# Amplifier.net
KiCad netlist of a schematic drawn in Altium Designer
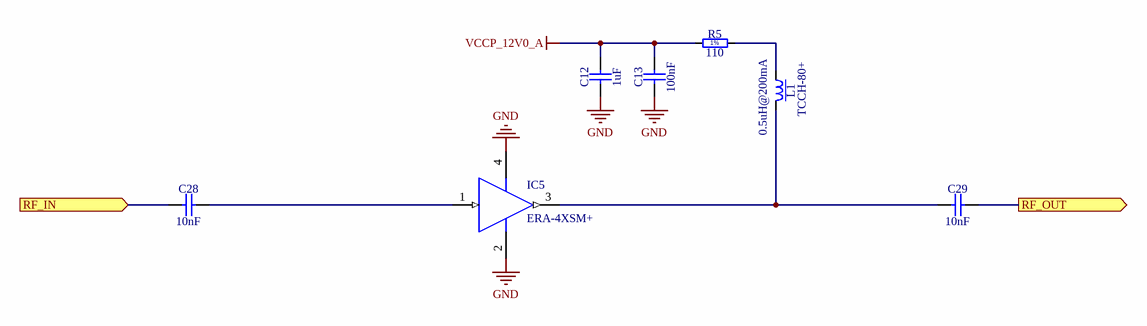
[diagram p0: Amplifier.SchDoc]

(export (version "E")
  (design (tool "Eeschema 10.0.6"))
  (components
    (comp (ref "C12")
      (value "1uF")
      (footprint "CAPC2012X140N")
      (description "Non-polarised capacitor")
      (fields
        (field (name "PART NUMBER") "CC0805_1UF_35V_20%_X7R")
        (field (name "VOLTAGE") "35V")
        (field (name "AUTHOR") "CERN DEM JLC")
      )
      (libsource (lib "Capacitors") (part "Capacitor - non polarized"))
    )
    (comp (ref "C13")
      (value "100nF")
      (footprint "CAPC1608X87N")
      (description "Non-polarised capacitor")
      (fields
        (field (name "PART NUMBER") "CC0603_100NF_50V_10%_X7R")
        (field (name "VOLTAGE") "50V")
        (field (name "AUTHOR") "CERN DEM JLC")
      )
      (libsource (lib "Capacitors") (part "Capacitor - non polarized"))
    )
    (comp (ref "C28")
      (value "10nF")
      (footprint "CAPC1005X55N")
      (description "Non-polarised capacitor")
      (fields
        (field (name "PART NUMBER") "CC0402_10NF_16V_10%_X7R")
        (field (name "VOLTAGE") "16V")
        (field (name "AUTHOR") "CERN DEM JLC")
      )
      (libsource (lib "Capacitors") (part "Capacitor - non polarized"))
    )
    (comp (ref "C29")
      (value "10nF")
      (footprint "CAPC1005X55N")
      (description "Non-polarised capacitor")
      (fields
        (field (name "PART NUMBER") "CC0402_10NF_16V_10%_X7R")
        (field (name "VOLTAGE") "16V")
        (field (name "AUTHOR") "CERN DEM JLC")
      )
      (libsource (lib "Capacitors") (part "Capacitor - non polarized"))
    )
    (comp (ref "IC5")
      (value "ERA-4XSM+")
      (footprint "MINI-CIRCUITS_WW107")
      (description "DC-4GHz Monolithic Amplifier")
      (fields (field (name "MANUFACTURER") "MINI-CIRCUITS") (field (name "AUTHOR") "CERN DEM JMW"))
      (libsource (lib "ICs And Semiconductors") (part "ERA-4XSM+"))
    )
    (comp (ref "L1")
      (value "0.5uH@200mA")
      (footprint "IND_MINI-CIRCUITS_GU1604")
      (description "50 Ohms, 50 to 8200 MHz RF Choke")
      (fields
        (field (name "PART NUMBER") "IND_MINI-CIRCUITS_TCCH-80+")
        (field (name "POWER") "200mA")
        (field (name "MANUFACTURER PART NUMBER") "TCCH-80+")
        (field (name "AUTHOR") "CERN DEM JLC")
      )
      (libsource (lib "Inductors & Transformers") (part "IND_MINI-CIRCUITS_TCCH-80+"))
    )
    (comp (ref "R5")
      (value "110")
      (footprint "RESC1005X40N")
      (description "Resistor - 1%")
      (fields
        (field (name "PART NUMBER") "R0402_110R_1%_0.0625W_100PPM")
        (field (name "POWER") "0.0625W")
        (field (name "AUTHOR") "CERN DEM JLC")
      )
      (libsource (lib "Resistors") (part "Resistor - 1%"))
    )
  )
  (nets
    (net (code "1") (name "/RF_IN") (class "Default")
      (node (ref "C28") (pin "1") (pinfunction "1_1") (pintype "passive"))
    )
    (net (code "2") (name "/RF_OUT") (class "Default")
      (node (ref "C29") (pin "2") (pinfunction "2_2") (pintype "passive"))
    )
    (net (code "3") (name "GND") (class "Default")
      (node (ref "C12") (pin "1") (pinfunction "1_1") (pintype "passive"))
      (node (ref "C13") (pin "1") (pinfunction "1_1") (pintype "passive"))
      (node (ref "IC5") (pin "2") (pinfunction "GND_2") (pintype "power_in"))
      (node (ref "IC5") (pin "4") (pinfunction "GND_4") (pintype "power_in"))
    )
    (net (code "4") (name "Net-(IC5-RF_IN)") (class "Default")
      (node (ref "C28") (pin "2") (pinfunction "2_2") (pintype "passive"))
      (node (ref "IC5") (pin "1") (pinfunction "RF_IN_1") (pintype "input"))
    )
    (net (code "5") (name "Net-(IC5-RF_OUT)") (class "Default")
      (node (ref "C29") (pin "1") (pinfunction "1_1") (pintype "passive"))
      (node (ref "IC5") (pin "3") (pinfunction "RF_OUT_3") (pintype "output"))
      (node (ref "L1") (pin "3") (pinfunction "3_3") (pintype "passive"))
    )
    (net (code "6") (name "Net-(L1-Pad1)") (class "Default")
      (node (ref "L1") (pin "1") (pinfunction "1_1") (pintype "passive"))
      (node (ref "R5") (pin "2") (pinfunction "2_2") (pintype "passive"))
    )
    (net (code "7") (name "VCCP_12V0_A") (class "Default")
      (node (ref "C12") (pin "2") (pinfunction "2_2") (pintype "passive"))
      (node (ref "C13") (pin "2") (pinfunction "2_2") (pintype "passive"))
      (node (ref "R5") (pin "1") (pinfunction "1_1") (pintype "passive"))
    )
  )
)
